# PART5_HPI_McBSP.net
KiCad netlist of a schematic drawn in Altium Designer
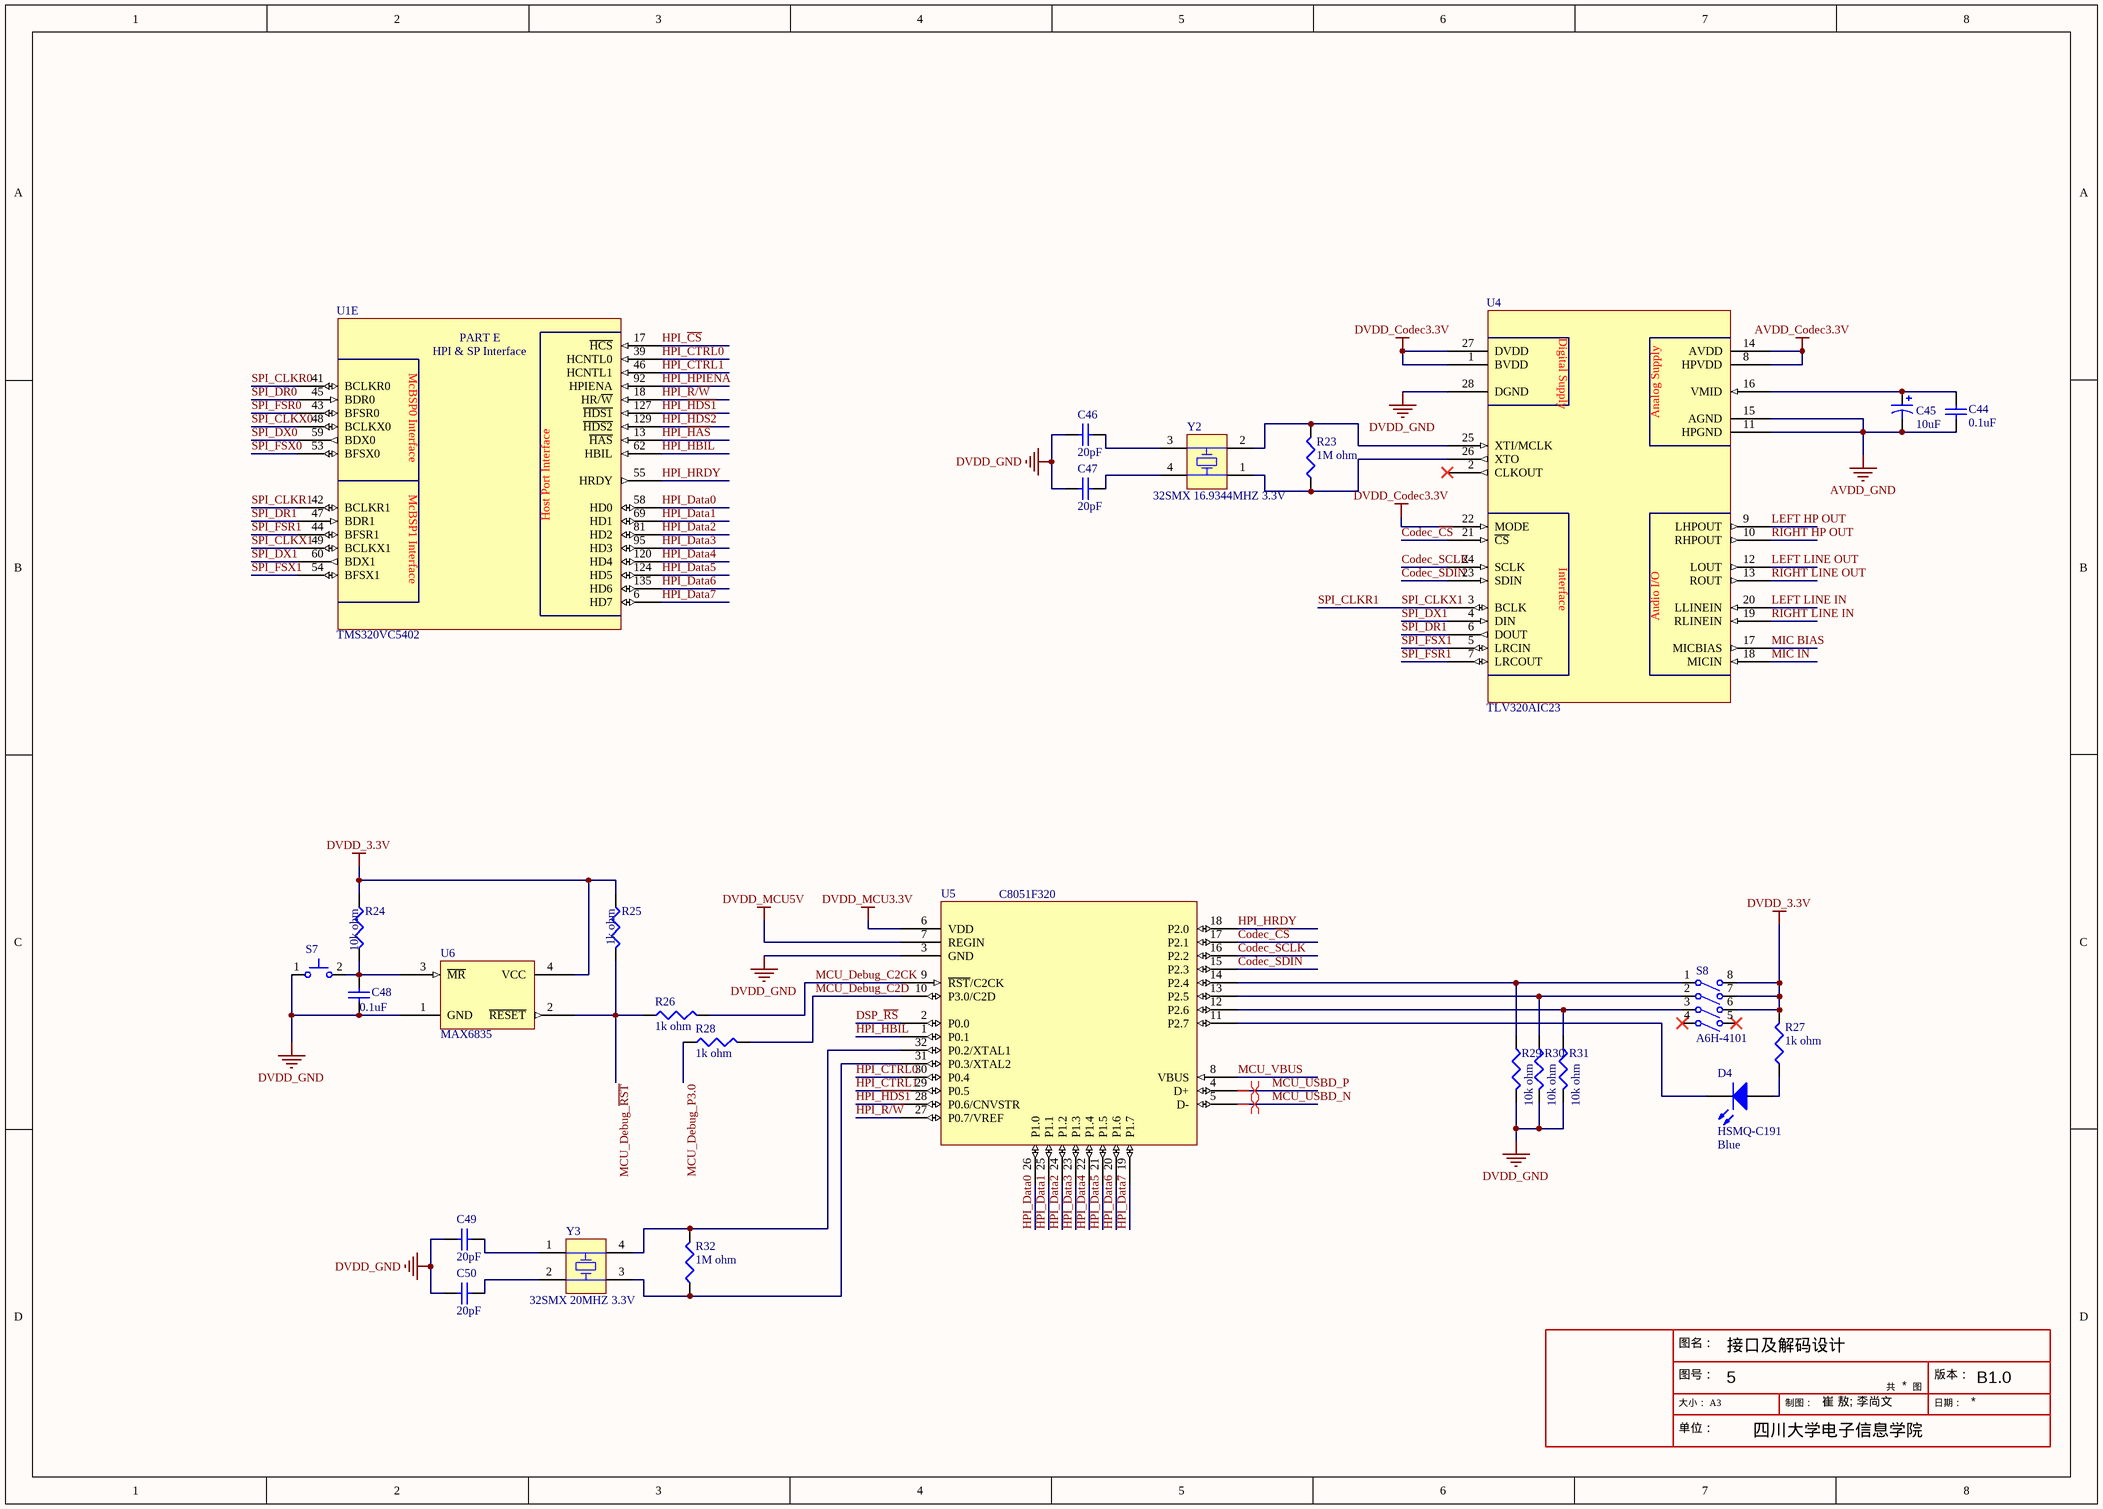
[diagram p0: PART5_HPI_McBSP.SchDoc]

(export (version "E")
  (design (tool "Eeschema 10.0.6"))
  (components
    (comp (ref "C44")
      (value "0.1uF")
      (footprint "1608[0603]")
      (description "贴片电容 1608")
      (fields (field (name "Comment") "Cap Semi") (field (name "PUBLISHER") "Altium Limited"))
      (libsource (lib "Miscellaneous Devices") (part "Cap Semi"))
    )
    (comp (ref "C45")
      (value "10uF")
      (footprint "C0805")
      (description "贴片钽电容 C0805")
      (fields (field (name "Comment") "Cap Tan") (field (name "PUBLISHER") "Altium Limited"))
      (libsource (lib "Miscellaneous Devices") (part "Cap Pol3"))
    )
    (comp (ref "C46")
      (value "20pF")
      (footprint "1608[0603]")
      (description "贴片电容 1608")
      (fields (field (name "Comment") "Cap Semi") (field (name "PUBLISHER") "Altium Limited"))
      (libsource (lib "Miscellaneous Devices") (part "Cap Semi"))
    )
    (comp (ref "C47")
      (value "20pF")
      (footprint "1608[0603]")
      (description "贴片电容 1608")
      (fields (field (name "Comment") "Cap Semi") (field (name "PUBLISHER") "Altium Limited"))
      (libsource (lib "Miscellaneous Devices") (part "Cap Semi"))
    )
    (comp (ref "C48")
      (value "0.1uF")
      (footprint "1608[0603]")
      (description "贴片电容 1608")
      (fields (field (name "Comment") "Cap Semi") (field (name "PUBLISHER") "Altium Limited"))
      (libsource (lib "Miscellaneous Devices") (part "Cap Semi"))
    )
    (comp (ref "C49")
      (value "20pF")
      (footprint "1608[0603]")
      (description "贴片电容 1608")
      (fields (field (name "Comment") "Cap Semi") (field (name "PUBLISHER") "Altium Limited"))
      (libsource (lib "Miscellaneous Devices") (part "Cap Semi"))
    )
    (comp (ref "C50")
      (value "20pF")
      (footprint "1608[0603]")
      (description "贴片电容 1608")
      (fields (field (name "Comment") "Cap Semi") (field (name "PUBLISHER") "Altium Limited"))
      (libsource (lib "Miscellaneous Devices") (part "Cap Semi"))
    )
    (comp (ref "D4")
      (value "HSMQ-C191")
      (footprint "1.6X0.8X0.6")
      (description "Top Mount Low Profile Chip LED, Green")
      (fields (field (name "LED_COLOUR") "Blue") (field (name "PUBLISHER") "Altium Limited"))
      (libsource (lib "Agilent Optoelectronic LED") (part "HSMQ-C191"))
    )
    (comp (ref "R23")
      (value "1M ohm")
      (footprint "J1-0603")
      (description "贴片电阻 0603")
      (fields (field (name "Comment") "Res3") (field (name "PUBLISHER") "Altium Limited"))
      (libsource (lib "Miscellaneous Devices") (part "Res3"))
    )
    (comp (ref "R24")
      (value "10k ohm")
      (footprint "J1-0603")
      (description "贴片电阻 0603")
      (fields (field (name "Comment") "Res3") (field (name "PUBLISHER") "Altium Limited"))
      (libsource (lib "Miscellaneous Devices") (part "Res3"))
    )
    (comp (ref "R25")
      (value "1k ohm")
      (footprint "J1-0603")
      (description "贴片电阻 0603")
      (fields (field (name "Comment") "Res3") (field (name "PUBLISHER") "Altium Limited"))
      (libsource (lib "Miscellaneous Devices") (part "Res3"))
    )
    (comp (ref "R26")
      (value "1k ohm")
      (footprint "J1-0603")
      (description "贴片电阻 0603")
      (fields (field (name "Comment") "Res3") (field (name "PUBLISHER") "Altium Limited"))
      (libsource (lib "Miscellaneous Devices") (part "Res3"))
    )
    (comp (ref "R27")
      (value "1k ohm")
      (footprint "J1-0603")
      (description "贴片电阻 0603")
      (fields (field (name "Comment") "Res3") (field (name "PUBLISHER") "Altium Limited"))
      (libsource (lib "Miscellaneous Devices") (part "Res3"))
    )
    (comp (ref "R28")
      (value "1k ohm")
      (footprint "J1-0603")
      (description "贴片电阻 0603")
      (fields (field (name "Comment") "Res3") (field (name "PUBLISHER") "Altium Limited"))
      (libsource (lib "Miscellaneous Devices") (part "Res3"))
    )
    (comp (ref "R29")
      (value "10k ohm")
      (footprint "J1-0603")
      (description "贴片电阻 0603")
      (fields (field (name "Comment") "Res3") (field (name "PUBLISHER") "Altium Limited"))
      (libsource (lib "Miscellaneous Devices") (part "Res3"))
    )
    (comp (ref "R30")
      (value "10k ohm")
      (footprint "J1-0603")
      (description "贴片电阻 0603")
      (fields (field (name "Comment") "Res3") (field (name "PUBLISHER") "Altium Limited"))
      (libsource (lib "Miscellaneous Devices") (part "Res3"))
    )
    (comp (ref "R31")
      (value "10k ohm")
      (footprint "J1-0603")
      (description "贴片电阻 0603")
      (fields (field (name "Comment") "Res3") (field (name "PUBLISHER") "Altium Limited"))
      (libsource (lib "Miscellaneous Devices") (part "Res3"))
    )
    (comp (ref "R32")
      (value "1M ohm")
      (footprint "J1-0603")
      (description "贴片电阻 0603")
      (fields (field (name "Comment") "Res3") (field (name "PUBLISHER") "Altium Limited"))
      (libsource (lib "Miscellaneous Devices") (part "Res3"))
    )
    (comp (ref "S7")
      (value "KSS221GLFS")
      (footprint "KSS-2G")
      (fields (field (name "PUBLISHER") "Altium Limited"))
      (libsource (lib "CK Switch") (part "KSS221GLFS"))
    )
    (comp (ref "S8")
      (value "A6H-4101")
      (footprint "A6H-4")
      (fields (field (name "PUBLISHER") "Altium Limited"))
      (libsource (lib "OMRON Switch DIP") (part "A6H-4101"))
    )
    (comp (ref "U1")
      (value "TMS320VC5402")
      (footprint "TMS320VC5401_PQFP144")
      (libsource (lib "TMS320VC5401") (part "TMS320VC5402"))
    )
    (comp (ref "U4")
      (value "TLV320AIC23")
      (footprint "TSOP65P640X120-28N")
      (libsource (lib "TMS320VC5401") (part "TLV320AIC23"))
    )
    (comp (ref "U5")
      (value "C8051F320")
      (footprint "TQFP80P900X900X160-32N")
      (libsource (lib "TMS320VC5401") (part "C8051F320"))
    )
    (comp (ref "U6") (value "MAX6835") (footprint "SC70-4") (libsource (lib "TMS320VC5401") (part "MAX6835")))
    (comp (ref "Y2")
      (value "32SMX 16.9344MHZ 3.3V")
      (footprint "32SMX")
      (description "Surface Mount Quartz Crystal")
      (fields (field (name "PUBLISHER") "Altium Limited"))
      (libsource (lib "C-MAC Crystal Oscillator") (part "32SMX"))
    )
    (comp (ref "Y3")
      (value "32SMX 20MHZ 3.3V")
      (footprint "32SMX")
      (description "Surface Mount Quartz Crystal")
      (fields (field (name "PUBLISHER") "Altium Limited"))
      (libsource (lib "") (part "32SMX_1"))
    )
  )
  (nets
    (net (code "1") (name "/Codec_SCLK") (class "Default")
      (node (ref "U4") (pin "24") (pinfunction "SCLK_24") (pintype "input"))
      (node (ref "U5") (pin "16") (pinfunction "P2.2_16") (pintype "bidirectional"))
    )
    (net (code "2") (name "/Codec_SDIN") (class "Default")
      (node (ref "U4") (pin "23") (pinfunction "SDIN_23") (pintype "input"))
      (node (ref "U5") (pin "15") (pinfunction "P2.3_15") (pintype "bidirectional"))
    )
    (net (code "3") (name "/Codec_~{CS}") (class "Default")
      (node (ref "U4") (pin "21") (pinfunction "~{CS}_21") (pintype "input"))
      (node (ref "U5") (pin "17") (pinfunction "P2.1_17") (pintype "bidirectional"))
    )
    (net (code "4") (name "/DSP_~{RS}") (class "Default")
      (node (ref "U5") (pin "2") (pinfunction "P0.0_2") (pintype "bidirectional"))
    )
    (net (code "5") (name "/HPI_CTRL0") (class "Default")
      (node (ref "U1") (pin "39") (pinfunction "HCNTL0_39") (pintype "input"))
      (node (ref "U5") (pin "30") (pinfunction "P0.4_30") (pintype "bidirectional"))
    )
    (net (code "6") (name "/HPI_CTRL1") (class "Default")
      (node (ref "U1") (pin "46") (pinfunction "HCNTL1_46") (pintype "input"))
      (node (ref "U5") (pin "29") (pinfunction "P0.5_29") (pintype "bidirectional"))
    )
    (net (code "7") (name "/HPI_Data0") (class "Default")
      (node (ref "U1") (pin "58") (pinfunction "HD0_58") (pintype "bidirectional"))
      (node (ref "U5") (pin "26") (pinfunction "P1.0_26") (pintype "bidirectional"))
    )
    (net (code "8") (name "/HPI_Data1") (class "Default")
      (node (ref "U1") (pin "69") (pinfunction "HD1_69") (pintype "bidirectional"))
      (node (ref "U5") (pin "25") (pinfunction "P1.1_25") (pintype "bidirectional"))
    )
    (net (code "9") (name "/HPI_Data2") (class "Default")
      (node (ref "U1") (pin "81") (pinfunction "HD2_81") (pintype "bidirectional"))
      (node (ref "U5") (pin "24") (pinfunction "P1.2_24") (pintype "bidirectional"))
    )
    (net (code "10") (name "/HPI_Data3") (class "Default")
      (node (ref "U1") (pin "95") (pinfunction "HD3_95") (pintype "bidirectional"))
      (node (ref "U5") (pin "23") (pinfunction "P1.3_23") (pintype "bidirectional"))
    )
    (net (code "11") (name "/HPI_Data4") (class "Default")
      (node (ref "U1") (pin "120") (pinfunction "HD4_120") (pintype "bidirectional"))
      (node (ref "U5") (pin "22") (pinfunction "P1.4_22") (pintype "bidirectional"))
    )
    (net (code "12") (name "/HPI_Data5") (class "Default")
      (node (ref "U1") (pin "124") (pinfunction "HD5_124") (pintype "bidirectional"))
      (node (ref "U5") (pin "21") (pinfunction "P1.5_21") (pintype "bidirectional"))
    )
    (net (code "13") (name "/HPI_Data6") (class "Default")
      (node (ref "U1") (pin "135") (pinfunction "HD6_135") (pintype "bidirectional"))
      (node (ref "U5") (pin "20") (pinfunction "P1.6_20") (pintype "bidirectional"))
    )
    (net (code "14") (name "/HPI_Data7") (class "Default")
      (node (ref "U1") (pin "6") (pinfunction "HD7_6") (pintype "bidirectional"))
      (node (ref "U5") (pin "19") (pinfunction "P1.7_19") (pintype "bidirectional"))
    )
    (net (code "15") (name "/HPI_HBIL") (class "Default")
      (node (ref "U1") (pin "62") (pinfunction "HBIL_62") (pintype "input"))
      (node (ref "U5") (pin "1") (pinfunction "P0.1_1") (pintype "bidirectional"))
    )
    (net (code "16") (name "/HPI_HPIENA") (class "Default")
      (node (ref "U1") (pin "92") (pinfunction "HPIENA_92") (pintype "input"))
    )
    (net (code "17") (name "/HPI_HRDY") (class "Default")
      (node (ref "U1") (pin "55") (pinfunction "HRDY_55") (pintype "output"))
      (node (ref "U5") (pin "18") (pinfunction "P2.0_18") (pintype "bidirectional"))
    )
    (net (code "18") (name "/HPI_R{slash}~{W}") (class "Default")
      (node (ref "U1") (pin "18") (pinfunction "HR/~{W}_18") (pintype "input"))
      (node (ref "U5") (pin "27") (pinfunction "P0.7/VREF_27") (pintype "bidirectional"))
    )
    (net (code "19") (name "/HPI_~{CS}") (class "Default")
      (node (ref "U1") (pin "17") (pinfunction "~{HCS}_17") (pintype "input"))
    )
    (net (code "20") (name "/HPI_~{HAS}") (class "Default")
      (node (ref "U1") (pin "13") (pinfunction "~{HAS}_13") (pintype "input"))
    )
    (net (code "21") (name "/HPI_~{HDS1}") (class "Default")
      (node (ref "U1") (pin "127") (pinfunction "~{HDS1}_127") (pintype "input"))
      (node (ref "U5") (pin "28") (pinfunction "P0.6/CNVSTR_28") (pintype "bidirectional"))
    )
    (net (code "22") (name "/HPI_~{HDS2}") (class "Default")
      (node (ref "U1") (pin "129") (pinfunction "~{HDS2}_129") (pintype "input"))
    )
    (net (code "23") (name "/LEFT HP OUT") (class "Default")
      (node (ref "U4") (pin "9") (pinfunction "LHPOUT_9") (pintype "output"))
    )
    (net (code "24") (name "/LEFT LINE IN") (class "Default")
      (node (ref "U4") (pin "20") (pinfunction "LLINEIN_20") (pintype "input"))
    )
    (net (code "25") (name "/LEFT LINE OUT") (class "Default")
      (node (ref "U4") (pin "12") (pinfunction "LOUT_12") (pintype "output"))
    )
    (net (code "26") (name "/MCU_Debug_C2CK") (class "Default")
      (node (ref "R26") (pin "2") (pinfunction "2_2") (pintype "passive"))
      (node (ref "U5") (pin "9") (pinfunction "~{RST}/C2CK_9") (pintype "input"))
    )
    (net (code "27") (name "/MCU_Debug_C2D") (class "Default")
      (node (ref "R28") (pin "2") (pinfunction "2_2") (pintype "passive"))
      (node (ref "U5") (pin "10") (pinfunction "P3.0/C2D_10") (pintype "bidirectional"))
    )
    (net (code "28") (name "/MCU_Debug_P3.0") (class "Default")
      (node (ref "R28") (pin "1") (pinfunction "1_1") (pintype "passive"))
    )
    (net (code "29") (name "/MCU_Debug_~{RST}") (class "Default")
      (node (ref "R25") (pin "2") (pinfunction "2_2") (pintype "passive"))
      (node (ref "R26") (pin "1") (pinfunction "1_1") (pintype "passive"))
      (node (ref "U6") (pin "2") (pinfunction "~{RESET}_2") (pintype "output"))
    )
    (net (code "30") (name "/MCU_USBD_N") (class "Default")
      (node (ref "U5") (pin "5") (pinfunction "D-_5") (pintype "bidirectional"))
    )
    (net (code "31") (name "/MCU_USBD_P") (class "Default")
      (node (ref "U5") (pin "4") (pinfunction "D+_4") (pintype "bidirectional"))
    )
    (net (code "32") (name "/MCU_VBUS") (class "Default")
      (node (ref "U5") (pin "8") (pinfunction "VBUS_8") (pintype "input"))
    )
    (net (code "33") (name "/MIC BIAS") (class "Default")
      (node (ref "U4") (pin "17") (pinfunction "MICBIAS_17") (pintype "output"))
    )
    (net (code "34") (name "/MIC IN") (class "Default")
      (node (ref "U4") (pin "18") (pinfunction "MICIN_18") (pintype "input"))
    )
    (net (code "35") (name "/RIGHT HP OUT") (class "Default")
      (node (ref "U4") (pin "10") (pinfunction "RHPOUT_10") (pintype "output"))
    )
    (net (code "36") (name "/RIGHT LINE IN") (class "Default")
      (node (ref "U4") (pin "19") (pinfunction "RLINEIN_19") (pintype "input"))
    )
    (net (code "37") (name "/RIGHT LINE OUT") (class "Default")
      (node (ref "U4") (pin "13") (pinfunction "ROUT_13") (pintype "output"))
    )
    (net (code "38") (name "/SPI_CLKR0") (class "Default")
      (node (ref "U1") (pin "41") (pinfunction "BCLKR0_41") (pintype "bidirectional"))
    )
    (net (code "39") (name "/SPI_CLKR1") (class "Default")
      (node (ref "U1") (pin "42") (pinfunction "BCLKR1_42") (pintype "bidirectional"))
      (node (ref "U1") (pin "49") (pinfunction "BCLKX1_49") (pintype "bidirectional"))
      (node (ref "U4") (pin "3") (pinfunction "BCLK_3") (pintype "bidirectional"))
    )
    (net (code "40") (name "/SPI_CLKX0") (class "Default")
      (node (ref "U1") (pin "48") (pinfunction "BCLKX0_48") (pintype "bidirectional"))
    )
    (net (code "41") (name "/SPI_DR0") (class "Default")
      (node (ref "U1") (pin "45") (pinfunction "BDR0_45") (pintype "input"))
    )
    (net (code "42") (name "/SPI_DR1") (class "Default")
      (node (ref "U1") (pin "47") (pinfunction "BDR1_47") (pintype "input"))
      (node (ref "U4") (pin "6") (pinfunction "DOUT_6") (pintype "output"))
    )
    (net (code "43") (name "/SPI_DX0") (class "Default")
      (node (ref "U1") (pin "59") (pinfunction "BDX0_59") (pintype "output"))
    )
    (net (code "44") (name "/SPI_DX1") (class "Default")
      (node (ref "U1") (pin "60") (pinfunction "BDX1_60") (pintype "output"))
      (node (ref "U4") (pin "4") (pinfunction "DIN_4") (pintype "input"))
    )
    (net (code "45") (name "/SPI_FSR0") (class "Default")
      (node (ref "U1") (pin "43") (pinfunction "BFSR0_43") (pintype "bidirectional"))
    )
    (net (code "46") (name "/SPI_FSR1") (class "Default")
      (node (ref "U1") (pin "44") (pinfunction "BFSR1_44") (pintype "bidirectional"))
      (node (ref "U4") (pin "7") (pinfunction "LRCOUT_7") (pintype "bidirectional"))
    )
    (net (code "47") (name "/SPI_FSX0") (class "Default")
      (node (ref "U1") (pin "53") (pinfunction "BFSX0_53") (pintype "bidirectional"))
    )
    (net (code "48") (name "/SPI_FSX1") (class "Default")
      (node (ref "U1") (pin "54") (pinfunction "BFSX1_54") (pintype "bidirectional"))
      (node (ref "U4") (pin "5") (pinfunction "LRCIN_5") (pintype "bidirectional"))
    )
    (net (code "49") (name "AVDD_Codec3.3V") (class "Default")
      (node (ref "U4") (pin "14") (pinfunction "AVDD_14") (pintype "power_in"))
      (node (ref "U4") (pin "8") (pinfunction "HPVDD_8") (pintype "power_in"))
    )
    (net (code "50") (name "AVDD_GND") (class "Default")
      (node (ref "C44") (pin "2") (pinfunction "2_2") (pintype "passive"))
      (node (ref "C45") (pin "2") (pinfunction "2_2") (pintype "passive"))
      (node (ref "U4") (pin "11") (pinfunction "HPGND_11") (pintype "passive"))
      (node (ref "U4") (pin "15") (pinfunction "AGND_15") (pintype "passive"))
    )
    (net (code "51") (name "DVDD_3.3V") (class "Default")
      (node (ref "R24") (pin "1") (pinfunction "1_1") (pintype "passive"))
      (node (ref "R25") (pin "1") (pinfunction "1_1") (pintype "passive"))
      (node (ref "R27") (pin "2") (pinfunction "2_2") (pintype "passive"))
      (node (ref "S8") (pin "6") (pinfunction "B3_6") (pintype "passive"))
      (node (ref "S8") (pin "7") (pinfunction "B2_7") (pintype "passive"))
      (node (ref "S8") (pin "8") (pinfunction "B1_8") (pintype "passive"))
      (node (ref "U6") (pin "4") (pinfunction "VCC_4") (pintype "power_in"))
    )
    (net (code "52") (name "DVDD_Codec3.3V") (class "Default")
      (node (ref "U4") (pin "1") (pinfunction "BVDD_1") (pintype "power_in"))
      (node (ref "U4") (pin "22") (pinfunction "MODE_22") (pintype "input"))
      (node (ref "U4") (pin "27") (pinfunction "DVDD_27") (pintype "power_in"))
    )
    (net (code "53") (name "DVDD_GND") (class "Default")
      (node (ref "C46") (pin "2") (pinfunction "2_2") (pintype "passive"))
      (node (ref "C47") (pin "2") (pinfunction "2_2") (pintype "passive"))
      (node (ref "C48") (pin "2") (pinfunction "2_2") (pintype "passive"))
      (node (ref "C49") (pin "2") (pinfunction "2_2") (pintype "passive"))
      (node (ref "C50") (pin "2") (pinfunction "2_2") (pintype "passive"))
      (node (ref "R29") (pin "2") (pinfunction "2_2") (pintype "passive"))
      (node (ref "R30") (pin "2") (pinfunction "2_2") (pintype "passive"))
      (node (ref "R31") (pin "2") (pinfunction "2_2") (pintype "passive"))
      (node (ref "S7") (pin "1") (pinfunction "1_1") (pintype "passive"))
      (node (ref "U4") (pin "28") (pinfunction "DGND_28") (pintype "passive"))
      (node (ref "U5") (pin "3") (pinfunction "GND_3") (pintype "passive"))
      (node (ref "U6") (pin "1") (pinfunction "GND_1") (pintype "power_in"))
    )
    (net (code "54") (name "DVDD_MCU3.3V") (class "Default")
      (node (ref "U5") (pin "6") (pinfunction "VDD_6") (pintype "power_in"))
    )
    (net (code "55") (name "DVDD_MCU5V") (class "Default")
      (node (ref "U5") (pin "7") (pinfunction "REGIN_7") (pintype "power_in"))
    )
    (net (code "56") (name "Net-(C46-Pad1)") (class "Default")
      (node (ref "C46") (pin "1") (pinfunction "1_1") (pintype "passive"))
      (node (ref "Y2") (pin "3") (pinfunction "OSC2_3") (pintype "passive"))
    )
    (net (code "57") (name "Net-(C47-Pad1)") (class "Default")
      (node (ref "C47") (pin "1") (pinfunction "1_1") (pintype "passive"))
      (node (ref "Y2") (pin "4") (pinfunction "OSC1_4") (pintype "passive"))
    )
    (net (code "58") (name "Net-(C49-Pad1)") (class "Default")
      (node (ref "C49") (pin "1") (pinfunction "1_1") (pintype "passive"))
      (node (ref "Y3") (pin "1") (pinfunction "OSC1_1") (pintype "passive"))
    )
    (net (code "59") (name "Net-(C50-Pad1)") (class "Default")
      (node (ref "C50") (pin "1") (pinfunction "1_1") (pintype "passive"))
      (node (ref "Y3") (pin "2") (pinfunction "OSC2_2") (pintype "passive"))
    )
    (net (code "60") (name "Net-(D4-A)") (class "Default")
      (node (ref "D4") (pin "1") (pinfunction "A_1") (pintype "passive"))
      (node (ref "R27") (pin "1") (pinfunction "1_1") (pintype "passive"))
    )
    (net (code "61") (name "Net-(D4-K)") (class "Default")
      (node (ref "D4") (pin "2") (pinfunction "K_2") (pintype "passive"))
      (node (ref "U5") (pin "11") (pinfunction "P2.7_11") (pintype "bidirectional"))
    )
    (net (code "62") (name "Net-(S8-A1)") (class "Default")
      (node (ref "R29") (pin "1") (pinfunction "1_1") (pintype "passive"))
      (node (ref "S8") (pin "1") (pinfunction "A1_1") (pintype "passive"))
      (node (ref "U5") (pin "14") (pinfunction "P2.4_14") (pintype "bidirectional"))
    )
    (net (code "63") (name "Net-(S8-A2)") (class "Default")
      (node (ref "R30") (pin "1") (pinfunction "1_1") (pintype "passive"))
      (node (ref "S8") (pin "2") (pinfunction "A2_2") (pintype "passive"))
      (node (ref "U5") (pin "13") (pinfunction "P2.5_13") (pintype "bidirectional"))
    )
    (net (code "64") (name "Net-(S8-A3)") (class "Default")
      (node (ref "R31") (pin "1") (pinfunction "1_1") (pintype "passive"))
      (node (ref "S8") (pin "3") (pinfunction "A3_3") (pintype "passive"))
      (node (ref "U5") (pin "12") (pinfunction "P2.6_12") (pintype "bidirectional"))
    )
    (net (code "65") (name "Net-(U4-VMID)") (class "Default")
      (node (ref "C44") (pin "1") (pinfunction "1_1") (pintype "passive"))
      (node (ref "C45") (pin "1") (pinfunction "1_1") (pintype "passive"))
      (node (ref "U4") (pin "16") (pinfunction "VMID_16") (pintype "input"))
    )
    (net (code "66") (name "Net-(U4-XTI{slash}MCLK)") (class "Default")
      (node (ref "R23") (pin "2") (pinfunction "2_2") (pintype "passive"))
      (node (ref "U4") (pin "25") (pinfunction "XTI/MCLK_25") (pintype "input"))
      (node (ref "Y2") (pin "2") (pinfunction "OSC2_2") (pintype "passive"))
    )
    (net (code "67") (name "Net-(U4-XTO)") (class "Default")
      (node (ref "R23") (pin "1") (pinfunction "1_1") (pintype "passive"))
      (node (ref "U4") (pin "26") (pinfunction "XTO_26") (pintype "output"))
      (node (ref "Y2") (pin "1") (pinfunction "OSC1_1") (pintype "passive"))
    )
    (net (code "68") (name "Net-(U5-P0.2{slash}XTAL1)") (class "Default")
      (node (ref "R32") (pin "2") (pinfunction "2_2") (pintype "passive"))
      (node (ref "U5") (pin "32") (pinfunction "P0.2/XTAL1_32") (pintype "bidirectional"))
      (node (ref "Y3") (pin "4") (pinfunction "OSC1_4") (pintype "passive"))
    )
    (net (code "69") (name "Net-(U5-P0.3{slash}XTAL2)") (class "Default")
      (node (ref "R32") (pin "1") (pinfunction "1_1") (pintype "passive"))
      (node (ref "U5") (pin "31") (pinfunction "P0.3/XTAL2_31") (pintype "bidirectional"))
      (node (ref "Y3") (pin "3") (pinfunction "OSC2_3") (pintype "passive"))
    )
    (net (code "70") (name "Net-(U6-~{MR})") (class "Default")
      (node (ref "C48") (pin "1") (pinfunction "1_1") (pintype "passive"))
      (node (ref "R24") (pin "2") (pinfunction "2_2") (pintype "passive"))
      (node (ref "S7") (pin "2") (pinfunction "2_2") (pintype "passive"))
      (node (ref "U6") (pin "3") (pinfunction "~{MR}_3") (pintype "input"))
    )
    (net (code "71") (name "unconnected-(S8-A4-Pad4)") (class "Default")
      (node (ref "S8") (pin "4") (pinfunction "A4_4") (pintype "passive+no_connect"))
    )
    (net (code "72") (name "unconnected-(S8-B4-Pad5)") (class "Default")
      (node (ref "S8") (pin "5") (pinfunction "B4_5") (pintype "passive+no_connect"))
    )
    (net (code "73") (name "unconnected-(U4-CLKOUT-Pad2)") (class "Default")
      (node (ref "U4") (pin "2") (pinfunction "CLKOUT_2") (pintype "output+no_connect"))
    )
  )
)
